# Schema_Soldeerbout2.net
KiCad netlist of a schematic drawn in Altium Designer
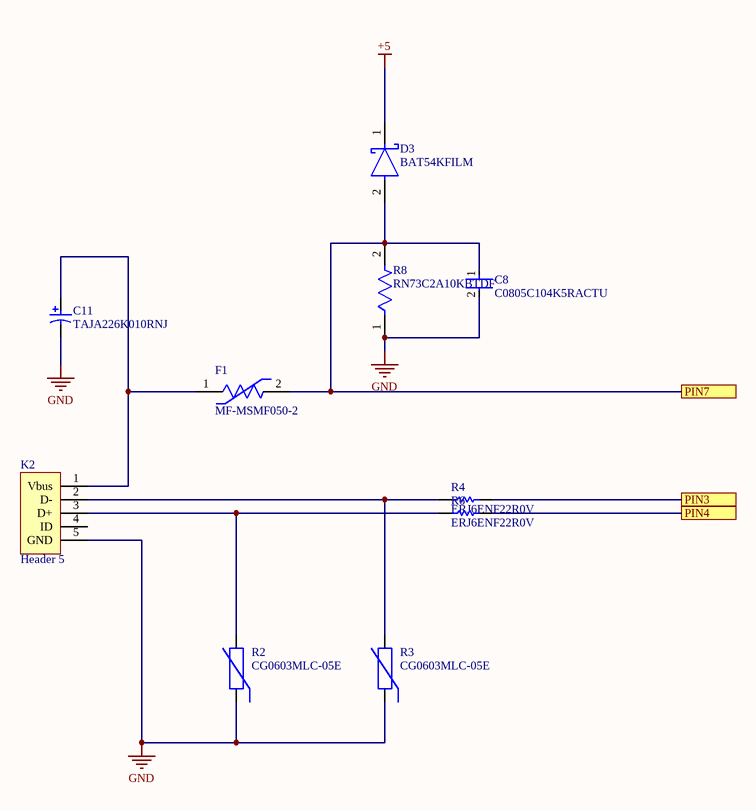
[diagram p0: Schema_Soldeerbout2.SchDoc]

(export (version "E")
  (design (tool "Eeschema 10.0.6"))
  (components
    (comp (ref "C8")
      (value "C0805C104K5RACTU")
      (footprint "FP-C0805C-DN-MFG")
      (description "CAP CER 0.1UF 50V X7R 0805")
      (fields
        (field (name "MANUFACTURER") "KEMET")
        (field (name "OCTOPART") "https://octopart.com/c0805c104k5ractu-kemet-143926")
      )
      (libsource (lib "Altium Content Vault") (part "b4654b650e69147ec39a6b967a45e02"))
    )
    (comp (ref "C11")
      (value "TAJA226K010RNJ")
      (footprint "AVX-TAJ-A-2_L")
      (description "Chip Capacitor, 22 uF, +/- 10%, 10 V, -55 to 125 degC, 1206 (3216 Metric), RoHS, Tape and Reel")
      (fields (field (name "MANUFACTURER") "AVX") (field (name "TOLERANCE") "10%"))
      (libsource (lib "Altium Content Vault") (part "CAP-P-2"))
    )
    (comp (ref "D3")
      (value "BAT54KFILM")
      (footprint "FP-SOD-523-MFG")
      (description "DIODE SCHOTTKY 40V 300MA SOD523")
      (fields
        (field (name "OCTOPART") "https://octopart.com/bat54kfilm-stmicroelectronics-39618022")
        (field (name "MANUFACTURER") "STMicroelectronics")
      )
      (libsource (lib "Altium Content Vault") (part "1d6ec82d83fb6aee721767c19dac4b9"))
    )
    (comp (ref "F1")
      (value "MF-MSMF050-2")
      (footprint "FP-MF-MSMF050-2-MFG")
      (description "PTC RESET FUSE 15V 500MA 1812")
      (fields
        (field (name "MANUFACTURER") "Bourns")
        (field (name "OCTOPART") "https://octopart.com/mf-msmf050-2-bourns-28047")
      )
      (libsource (lib "Altium Content Vault") (part "fc31388045fc42ab786d6d00b506e9f"))
    )
    (comp (ref "K2")
      (value "Header 5")
      (footprint "HDR1X5")
      (description "Header, 5-Pin")
      (fields (field (name "PUBLISHER") "Altium Limited"))
      (libsource (lib "Miscellaneous Connectors") (part "Header 5"))
    )
    (comp (ref "R2")
      (value "CG0603MLC-05E")
      (footprint "BOUR-CG0603-2_V")
      (description "ESD Protector, 5 V Supply, -40 to 85 degC, 1.6 x 0.8 x 0.55 mm SMD, RoHS, Tape and Reel")
      (fields (field (name "MANUFACTURER") "Bourns"))
      (libsource (lib "Altium Content Vault") (part "BOUR-VSR-2"))
    )
    (comp (ref "R3")
      (value "CG0603MLC-05E")
      (footprint "BOUR-CG0603-2_V")
      (description "ESD Protector, 5 V Supply, -40 to 85 degC, 1.6 x 0.8 x 0.55 mm SMD, RoHS, Tape and Reel")
      (fields (field (name "MANUFACTURER") "Bourns"))
      (libsource (lib "Altium Content Vault") (part "BOUR-VSR-2"))
    )
    (comp (ref "R4")
      (value "ERJ6ENF22R0V")
      (footprint "RESC2013X70X40LL20T20")
      (fields (field (name "MANUFACTURER") "Panasonic"))
      (libsource (lib "Altium Content Vault") (part "RES"))
    )
    (comp (ref "R6")
      (value "ERJ6ENF22R0V")
      (footprint "RESC2013X70X40LL20T20")
      (fields (field (name "MANUFACTURER") "Panasonic"))
      (libsource (lib "Altium Content Vault") (part "RES"))
    )
    (comp (ref "R8")
      (value "RN73C2A10KBTDF")
      (footprint "FP-RN732A-MFG")
      (description "SMD Chip Resistor, Thin Film, 10KΩ, 100 V, 0805 [2012 Metric], 100 mW, 0.1%, RN73 Series")
      (fields
        (field (name "OCTOPART") "https://octopart.com/rn73c2a10kbtdf-te+connectivity-21400356")
        (field (name "MANUFACTURER") "TE Connectivity")
      )
      (libsource (lib "Altium Content Vault") (part "1029c3af85768c4190bb7ad29bc67b5"))
    )
  )
  (nets
    (net (code "1") (name "+5") (class "Default")
      (node (ref "D3") (pin "1") (pinfunction "C_1") (pintype "passive"))
    )
    (net (code "2") (name "/PIN3") (class "Default")
      (node (ref "R4") (pin "2") (pinfunction "2_2") (pintype "passive"))
    )
    (net (code "3") (name "/PIN4") (class "Default")
      (node (ref "R6") (pin "2") (pinfunction "2_2") (pintype "passive"))
    )
    (net (code "4") (name "/PIN7") (class "Default")
      (node (ref "C8") (pin "1") (pinfunction "1_1") (pintype "passive"))
      (node (ref "D3") (pin "2") (pinfunction "A_2") (pintype "passive"))
      (node (ref "F1") (pin "2") (pinfunction "2_2") (pintype "passive"))
      (node (ref "R8") (pin "2") (pinfunction "2_2") (pintype "passive"))
    )
    (net (code "5") (name "GND") (class "Default")
      (node (ref "C11") (pin "2") (pinfunction "2_2") (pintype "passive"))
      (node (ref "C8") (pin "2") (pinfunction "2_2") (pintype "passive"))
      (node (ref "K2") (pin "5") (pinfunction "GND_5") (pintype "passive"))
      (node (ref "R2") (pin "1") (pinfunction "1_1") (pintype "passive"))
      (node (ref "R3") (pin "1") (pinfunction "1_1") (pintype "passive"))
      (node (ref "R8") (pin "1") (pinfunction "1_1") (pintype "passive"))
    )
    (net (code "6") (name "Net-(K2-D+)") (class "Default")
      (node (ref "K2") (pin "3") (pinfunction "D+_3") (pintype "passive"))
      (node (ref "R2") (pin "2") (pinfunction "2_2") (pintype "passive"))
      (node (ref "R6") (pin "1") (pinfunction "1_1") (pintype "passive"))
    )
    (net (code "7") (name "Net-(K2-D-)") (class "Default")
      (node (ref "K2") (pin "2") (pinfunction "D-_2") (pintype "passive"))
      (node (ref "R3") (pin "2") (pinfunction "2_2") (pintype "passive"))
      (node (ref "R4") (pin "1") (pinfunction "1_1") (pintype "passive"))
    )
    (net (code "8") (name "Net-(K2-Vbus)") (class "Default")
      (node (ref "C11") (pin "1") (pinfunction "1_1") (pintype "passive"))
      (node (ref "F1") (pin "1") (pinfunction "1_1") (pintype "passive"))
      (node (ref "K2") (pin "1") (pinfunction "Vbus_1") (pintype "passive"))
    )
    (net (code "9") (name "unconnected-(K2-ID-Pad4)") (class "Default")
      (node (ref "K2") (pin "4") (pinfunction "ID_4") (pintype "passive"))
    )
  )
)
